# oled_mod.net
KiCad netlist of a schematic drawn in Altium Designer
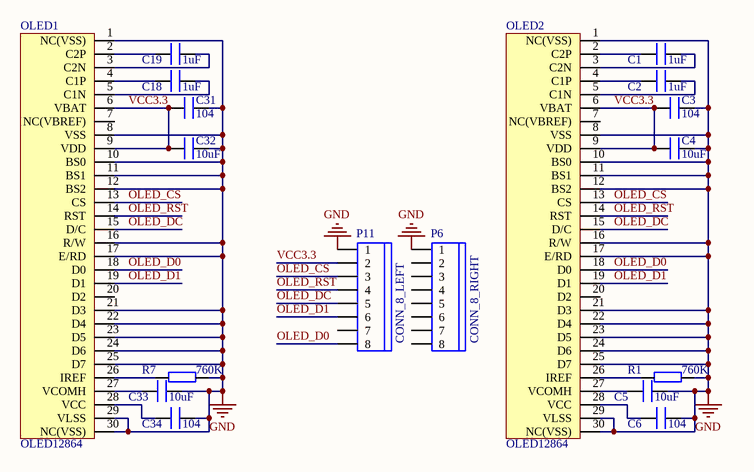
[diagram p0: oled_mod.SchDoc]

(export (version "E")
  (design (tool "Eeschema 10.0.6"))
  (components
    (comp (ref "C1")
      (value "1uF")
      (footprint "C 0603_L")
      (libsource (lib "WarShip V3 STM32103封装库") (part "C"))
    )
    (comp (ref "C2")
      (value "1uF")
      (footprint "C 0603_L")
      (libsource (lib "WarShip V3 STM32103封装库") (part "C"))
    )
    (comp (ref "C3")
      (value "104")
      (footprint "C 0603_L")
      (libsource (lib "WarShip V3 STM32103封装库") (part "C"))
    )
    (comp (ref "C4")
      (value "10uF")
      (footprint "C 0603_L")
      (libsource (lib "WarShip V3 STM32103封装库") (part "C"))
    )
    (comp (ref "C5")
      (value "10uF")
      (footprint "C 0603_L")
      (libsource (lib "WarShip V3 STM32103封装库") (part "C"))
    )
    (comp (ref "C6")
      (value "104")
      (footprint "C 0603_L")
      (libsource (lib "WarShip V3 STM32103封装库") (part "C"))
    )
    (comp (ref "C18")
      (value "1uF")
      (footprint "C 0603_L")
      (libsource (lib "WarShip V3 STM32103封装库") (part "C"))
    )
    (comp (ref "C19")
      (value "1uF")
      (footprint "C 0603_L")
      (libsource (lib "WarShip V3 STM32103封装库") (part "C"))
    )
    (comp (ref "C31")
      (value "104")
      (footprint "C 0603_L")
      (libsource (lib "WarShip V3 STM32103封装库") (part "C"))
    )
    (comp (ref "C32")
      (value "10uF")
      (footprint "C 0603_L")
      (libsource (lib "WarShip V3 STM32103封装库") (part "C"))
    )
    (comp (ref "C33")
      (value "10uF")
      (footprint "C 0603_L")
      (libsource (lib "WarShip V3 STM32103封装库") (part "C"))
    )
    (comp (ref "C34")
      (value "104")
      (footprint "C 0603_L")
      (libsource (lib "WarShip V3 STM32103封装库") (part "C"))
    )
    (comp (ref "OLED1")
      (value "OLED12864")
      (footprint "OLED_0.96")
      (libsource (lib "OLED模块封装库") (part "OLED12864"))
    )
    (comp (ref "OLED2")
      (value "OLED12864")
      (footprint "OLED_0.96")
      (libsource (lib "OLED模块封装库") (part "OLED12864"))
    )
    (comp (ref "P6")
      (value "CONN_8_RIGHT")
      (footprint "HEADER8-2.0MM")
      (libsource (lib "ATK-2014-09-12") (part "HEAD8"))
    )
    (comp (ref "P11")
      (value "CONN_8_LEFT")
      (footprint "HEADER8-2.0MM")
      (libsource (lib "ATK-2014-09-12") (part "HEAD8"))
    )
    (comp (ref "R1")
      (value "760K")
      (footprint "R 0603_L")
      (libsource (lib "WarShip V3 STM32103封装库") (part "R"))
    )
    (comp (ref "R7")
      (value "760K")
      (footprint "R 0603_L")
      (libsource (lib "WarShip V3 STM32103封装库") (part "R"))
    )
  )
  (nets
    (net (code "1") (name "/OLED_CS") (class "Default")
      (node (ref "OLED1") (pin "13") (pinfunction "CS_13") (pintype "passive"))
      (node (ref "OLED2") (pin "13") (pinfunction "CS_13") (pintype "passive"))
      (node (ref "P11") (pin "3") (pinfunction "3_3") (pintype "passive"))
    )
    (net (code "2") (name "/OLED_D0") (class "Default")
      (node (ref "OLED1") (pin "18") (pinfunction "D0_18") (pintype "passive"))
      (node (ref "OLED2") (pin "18") (pinfunction "D0_18") (pintype "passive"))
      (node (ref "P11") (pin "8") (pinfunction "8_8") (pintype "passive"))
    )
    (net (code "3") (name "/OLED_D1") (class "Default")
      (node (ref "OLED1") (pin "19") (pinfunction "D1_19") (pintype "passive"))
      (node (ref "OLED2") (pin "19") (pinfunction "D1_19") (pintype "passive"))
      (node (ref "P11") (pin "6") (pinfunction "6_6") (pintype "passive"))
    )
    (net (code "4") (name "/OLED_DC") (class "Default")
      (node (ref "OLED1") (pin "15") (pinfunction "D/C_15") (pintype "passive"))
      (node (ref "OLED2") (pin "15") (pinfunction "D/C_15") (pintype "passive"))
      (node (ref "P11") (pin "5") (pinfunction "5_5") (pintype "passive"))
    )
    (net (code "5") (name "/OLED_RST") (class "Default")
      (node (ref "OLED1") (pin "14") (pinfunction "RST_14") (pintype "passive"))
      (node (ref "OLED2") (pin "14") (pinfunction "RST_14") (pintype "passive"))
      (node (ref "P11") (pin "4") (pinfunction "4_4") (pintype "passive"))
    )
    (net (code "6") (name "/VCC3.3") (class "Default")
      (node (ref "C3") (pin "2") (pintype "passive"))
      (node (ref "C31") (pin "2") (pintype "passive"))
      (node (ref "C32") (pin "2") (pintype "passive"))
      (node (ref "C4") (pin "2") (pintype "passive"))
      (node (ref "OLED1") (pin "6") (pinfunction "VBAT_6") (pintype "passive"))
      (node (ref "OLED1") (pin "9") (pinfunction "VDD_9") (pintype "passive"))
      (node (ref "OLED2") (pin "6") (pinfunction "VBAT_6") (pintype "passive"))
      (node (ref "OLED2") (pin "9") (pinfunction "VDD_9") (pintype "passive"))
      (node (ref "P11") (pin "2") (pinfunction "2_2") (pintype "passive"))
    )
    (net (code "7") (name "GND") (class "Default")
      (node (ref "C3") (pin "1") (pintype "passive"))
      (node (ref "C31") (pin "1") (pintype "passive"))
      (node (ref "C32") (pin "1") (pintype "passive"))
      (node (ref "C33") (pin "1") (pintype "passive"))
      (node (ref "C34") (pin "1") (pintype "passive"))
      (node (ref "C4") (pin "1") (pintype "passive"))
      (node (ref "C5") (pin "1") (pintype "passive"))
      (node (ref "C6") (pin "1") (pintype "passive"))
      (node (ref "OLED1") (pin "1") (pinfunction "NC(VSS)_1") (pintype "passive"))
      (node (ref "OLED1") (pin "10") (pinfunction "BS0_10") (pintype "passive"))
      (node (ref "OLED1") (pin "11") (pinfunction "BS1_11") (pintype "passive"))
      (node (ref "OLED1") (pin "12") (pinfunction "BS2_12") (pintype "passive"))
      (node (ref "OLED1") (pin "16") (pinfunction "R/W_16") (pintype "passive"))
      (node (ref "OLED1") (pin "17") (pinfunction "E/RD_17") (pintype "passive"))
      (node (ref "OLED1") (pin "21") (pinfunction "D3_21") (pintype "passive"))
      (node (ref "OLED1") (pin "22") (pinfunction "D4_22") (pintype "passive"))
      (node (ref "OLED1") (pin "23") (pinfunction "D5_23") (pintype "passive"))
      (node (ref "OLED1") (pin "24") (pinfunction "D6_24") (pintype "passive"))
      (node (ref "OLED1") (pin "25") (pinfunction "D7_25") (pintype "passive"))
      (node (ref "OLED1") (pin "29") (pinfunction "VLSS_29") (pintype "passive"))
      (node (ref "OLED1") (pin "30") (pinfunction "NC(VSS)_30") (pintype "passive"))
      (node (ref "OLED1") (pin "8") (pinfunction "VSS_8") (pintype "passive"))
      (node (ref "OLED2") (pin "1") (pinfunction "NC(VSS)_1") (pintype "passive"))
      (node (ref "OLED2") (pin "10") (pinfunction "BS0_10") (pintype "passive"))
      (node (ref "OLED2") (pin "11") (pinfunction "BS1_11") (pintype "passive"))
      (node (ref "OLED2") (pin "12") (pinfunction "BS2_12") (pintype "passive"))
      (node (ref "OLED2") (pin "16") (pinfunction "R/W_16") (pintype "passive"))
      (node (ref "OLED2") (pin "17") (pinfunction "E/RD_17") (pintype "passive"))
      (node (ref "OLED2") (pin "21") (pinfunction "D3_21") (pintype "passive"))
      (node (ref "OLED2") (pin "22") (pinfunction "D4_22") (pintype "passive"))
      (node (ref "OLED2") (pin "23") (pinfunction "D5_23") (pintype "passive"))
      (node (ref "OLED2") (pin "24") (pinfunction "D6_24") (pintype "passive"))
      (node (ref "OLED2") (pin "25") (pinfunction "D7_25") (pintype "passive"))
      (node (ref "OLED2") (pin "29") (pinfunction "VLSS_29") (pintype "passive"))
      (node (ref "OLED2") (pin "30") (pinfunction "NC(VSS)_30") (pintype "passive"))
      (node (ref "OLED2") (pin "8") (pinfunction "VSS_8") (pintype "passive"))
      (node (ref "P11") (pin "1") (pinfunction "1_1") (pintype "passive"))
      (node (ref "P6") (pin "1") (pinfunction "1_1") (pintype "passive"))
      (node (ref "R1") (pin "1") (pintype "passive"))
      (node (ref "R7") (pin "1") (pintype "passive"))
    )
    (net (code "8") (name "Net-(OLED1-C1N)") (class "Default")
      (node (ref "C18") (pin "1") (pintype "passive"))
      (node (ref "OLED1") (pin "5") (pinfunction "C1N_5") (pintype "passive"))
    )
    (net (code "9") (name "Net-(OLED1-C1P)") (class "Default")
      (node (ref "C18") (pin "2") (pintype "passive"))
      (node (ref "OLED1") (pin "4") (pinfunction "C1P_4") (pintype "passive"))
    )
    (net (code "10") (name "Net-(OLED1-C2N)") (class "Default")
      (node (ref "C19") (pin "1") (pintype "passive"))
      (node (ref "OLED1") (pin "3") (pinfunction "C2N_3") (pintype "passive"))
    )
    (net (code "11") (name "Net-(OLED1-C2P)") (class "Default")
      (node (ref "C19") (pin "2") (pintype "passive"))
      (node (ref "OLED1") (pin "2") (pinfunction "C2P_2") (pintype "passive"))
    )
    (net (code "12") (name "Net-(OLED1-IREF)") (class "Default")
      (node (ref "OLED1") (pin "26") (pinfunction "IREF_26") (pintype "passive"))
      (node (ref "R7") (pin "2") (pintype "passive"))
    )
    (net (code "13") (name "Net-(OLED1-VCC)") (class "Default")
      (node (ref "C34") (pin "2") (pintype "passive"))
      (node (ref "OLED1") (pin "28") (pinfunction "VCC_28") (pintype "passive"))
    )
    (net (code "14") (name "Net-(OLED1-VCOMH)") (class "Default")
      (node (ref "C33") (pin "2") (pintype "passive"))
      (node (ref "OLED1") (pin "27") (pinfunction "VCOMH_27") (pintype "passive"))
    )
    (net (code "15") (name "Net-(OLED2-C1N)") (class "Default")
      (node (ref "C2") (pin "1") (pintype "passive"))
      (node (ref "OLED2") (pin "5") (pinfunction "C1N_5") (pintype "passive"))
    )
    (net (code "16") (name "Net-(OLED2-C1P)") (class "Default")
      (node (ref "C2") (pin "2") (pintype "passive"))
      (node (ref "OLED2") (pin "4") (pinfunction "C1P_4") (pintype "passive"))
    )
    (net (code "17") (name "Net-(OLED2-C2N)") (class "Default")
      (node (ref "C1") (pin "1") (pintype "passive"))
      (node (ref "OLED2") (pin "3") (pinfunction "C2N_3") (pintype "passive"))
    )
    (net (code "18") (name "Net-(OLED2-C2P)") (class "Default")
      (node (ref "C1") (pin "2") (pintype "passive"))
      (node (ref "OLED2") (pin "2") (pinfunction "C2P_2") (pintype "passive"))
    )
    (net (code "19") (name "Net-(OLED2-IREF)") (class "Default")
      (node (ref "OLED2") (pin "26") (pinfunction "IREF_26") (pintype "passive"))
      (node (ref "R1") (pin "2") (pintype "passive"))
    )
    (net (code "20") (name "Net-(OLED2-VCC)") (class "Default")
      (node (ref "C6") (pin "2") (pintype "passive"))
      (node (ref "OLED2") (pin "28") (pinfunction "VCC_28") (pintype "passive"))
    )
    (net (code "21") (name "Net-(OLED2-VCOMH)") (class "Default")
      (node (ref "C5") (pin "2") (pintype "passive"))
      (node (ref "OLED2") (pin "27") (pinfunction "VCOMH_27") (pintype "passive"))
    )
    (net (code "22") (name "unconnected-(OLED1-D2-Pad20)") (class "Default")
      (node (ref "OLED1") (pin "20") (pinfunction "D2_20") (pintype "passive"))
    )
    (net (code "23") (name "unconnected-(OLED1-NC(VBREF)-Pad7)") (class "Default")
      (node (ref "OLED1") (pin "7") (pinfunction "NC(VBREF)_7") (pintype "passive"))
    )
    (net (code "24") (name "unconnected-(OLED2-D2-Pad20)") (class "Default")
      (node (ref "OLED2") (pin "20") (pinfunction "D2_20") (pintype "passive"))
    )
    (net (code "25") (name "unconnected-(OLED2-NC(VBREF)-Pad7)") (class "Default")
      (node (ref "OLED2") (pin "7") (pinfunction "NC(VBREF)_7") (pintype "passive"))
    )
    (net (code "26") (name "unconnected-(P6-Pad2)") (class "Default")
      (node (ref "P6") (pin "2") (pinfunction "2_2") (pintype "passive"))
    )
    (net (code "27") (name "unconnected-(P6-Pad3)") (class "Default")
      (node (ref "P6") (pin "3") (pinfunction "3_3") (pintype "passive"))
    )
    (net (code "28") (name "unconnected-(P6-Pad4)") (class "Default")
      (node (ref "P6") (pin "4") (pinfunction "4_4") (pintype "passive"))
    )
    (net (code "29") (name "unconnected-(P6-Pad5)") (class "Default")
      (node (ref "P6") (pin "5") (pinfunction "5_5") (pintype "passive"))
    )
    (net (code "30") (name "unconnected-(P6-Pad6)") (class "Default")
      (node (ref "P6") (pin "6") (pinfunction "6_6") (pintype "passive"))
    )
    (net (code "31") (name "unconnected-(P6-Pad7)") (class "Default")
      (node (ref "P6") (pin "7") (pinfunction "7_7") (pintype "passive"))
    )
    (net (code "32") (name "unconnected-(P6-Pad8)") (class "Default")
      (node (ref "P6") (pin "8") (pinfunction "8_8") (pintype "passive"))
    )
    (net (code "33") (name "unconnected-(P11-Pad7)") (class "Default")
      (node (ref "P11") (pin "7") (pinfunction "7_7") (pintype "passive"))
    )
  )
)
